# 05_POWER_EFUSE.net
KiCad netlist of a schematic drawn in Altium Designer
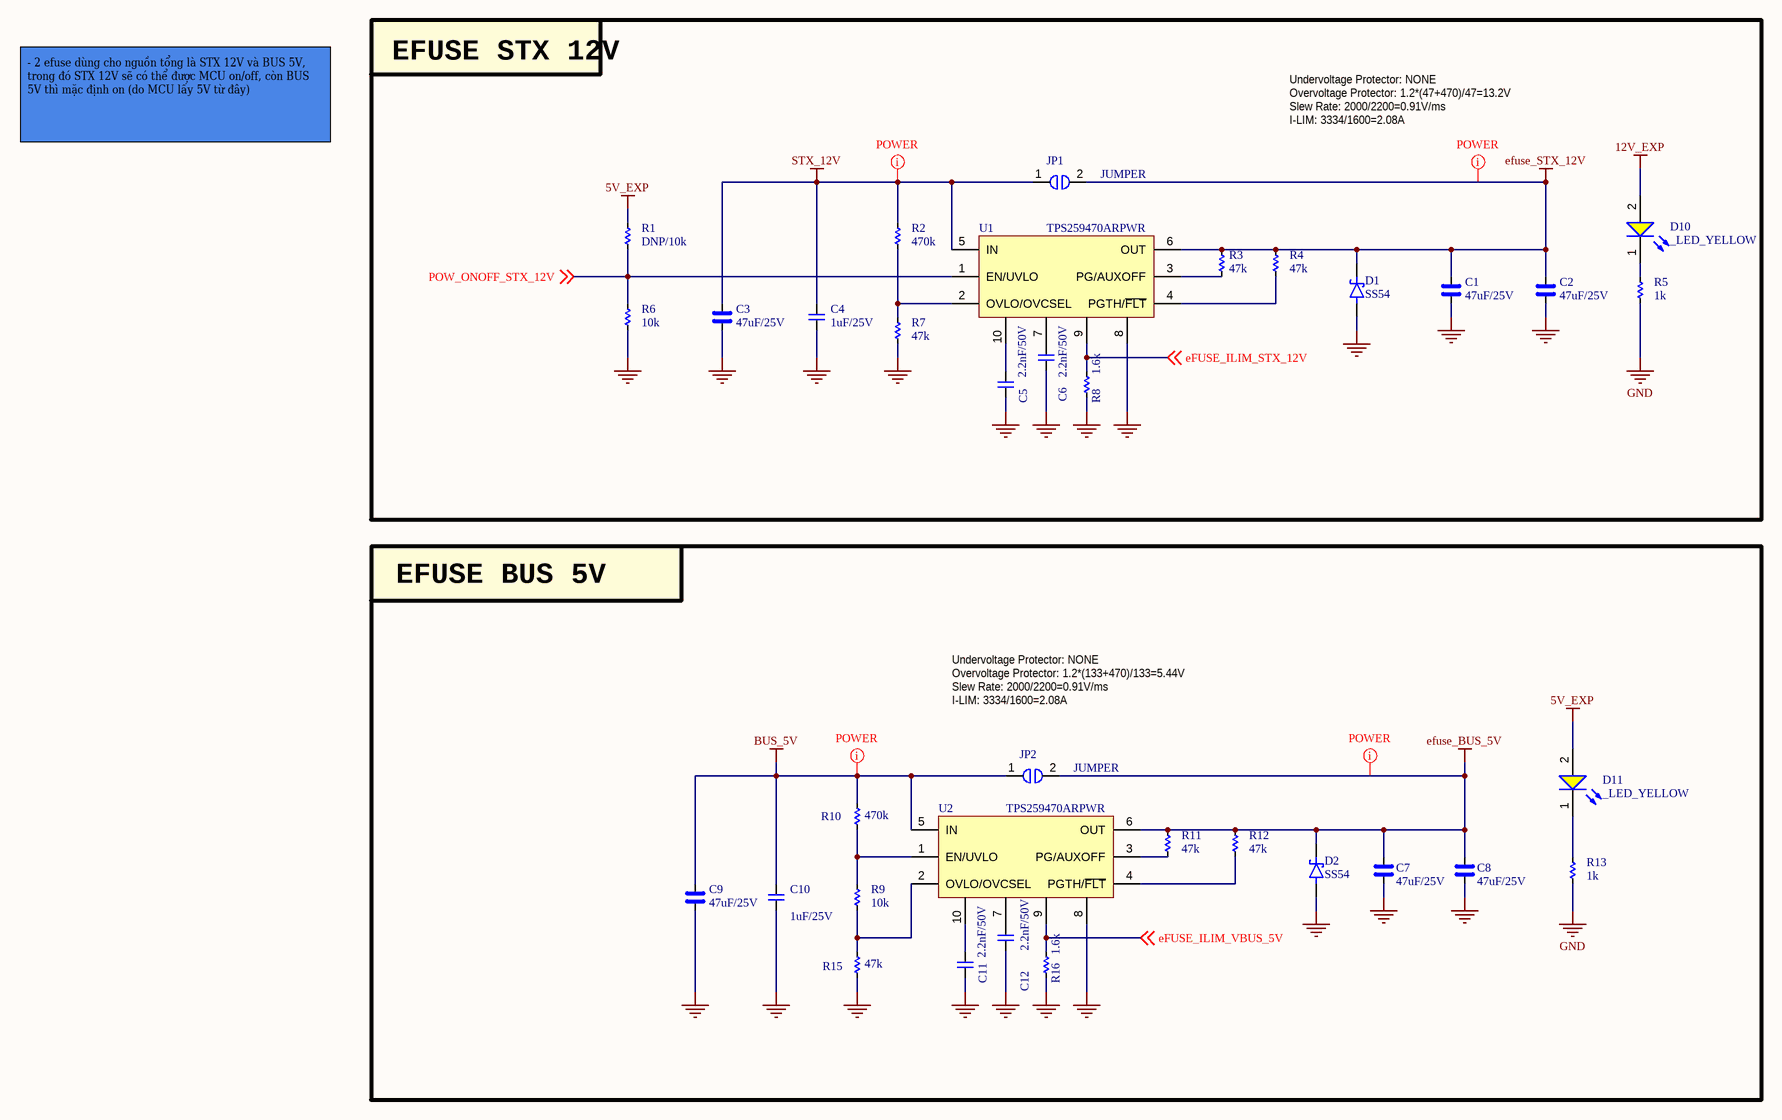
[diagram p0: 05_POWER_EFUSE.SchDoc]

(export (version "E")
  (design (tool "Eeschema 10.0.6"))
  (components
    (comp (ref "C1")
      (value "47uF/25V")
      (footprint "CAP_C_3225X80")
      (description "CAP High Value")
      (libsource (lib "LABLIB") (part "_CAP_C_High_2"))
    )
    (comp (ref "C2")
      (value "47uF/25V")
      (footprint "CAP_C_3225X80")
      (description "CAP High Value")
      (libsource (lib "LABLIB") (part "_CAP_C_High_2"))
    )
    (comp (ref "C3")
      (value "47uF/25V")
      (footprint "CAP_C_3225X80")
      (description "CAP High Value")
      (libsource (lib "LABLIB") (part "_CAP_C_High_2"))
    )
    (comp (ref "C4")
      (value "1uF/25V")
      (footprint "CAP_C_1005X60")
      (description "CAP")
      (libsource (lib "LABLIB") (part "_CAP_C_2"))
    )
    (comp (ref "C5")
      (value "2.2nF/50V")
      (footprint "CAP_C_1005X60")
      (description "CAP")
      (libsource (lib "LABLIB") (part "_CAP_C_2"))
    )
    (comp (ref "C6")
      (value "2.2nF/50V")
      (footprint "CAP_C_1005X60")
      (description "CAP")
      (libsource (lib "LABLIB") (part "_CAP_C_2"))
    )
    (comp (ref "C7")
      (value "47uF/25V")
      (footprint "CAP_C_3225X80")
      (description "CAP High Value")
      (libsource (lib "LABLIB") (part "_CAP_C_High_2"))
    )
    (comp (ref "C8")
      (value "47uF/25V")
      (footprint "CAP_C_3225X80")
      (description "CAP High Value")
      (libsource (lib "LABLIB") (part "_CAP_C_High_2"))
    )
    (comp (ref "C9")
      (value "47uF/25V")
      (footprint "CAP_C_3225X80")
      (description "CAP High Value")
      (libsource (lib "LABLIB") (part "_CAP_C_High_2"))
    )
    (comp (ref "C10")
      (value "1uF/25V")
      (footprint "CAP_C_1005X60")
      (description "CAP")
      (libsource (lib "LABLIB") (part "_CAP_C_2"))
    )
    (comp (ref "C11")
      (value "2.2nF/50V")
      (footprint "CAP_C_1005X60")
      (description "CAP")
      (libsource (lib "LABLIB") (part "_CAP_C_2"))
    )
    (comp (ref "C12")
      (value "2.2nF/50V")
      (footprint "CAP_C_1005X60")
      (description "CAP")
      (libsource (lib "LABLIB") (part "_CAP_C_2"))
    )
    (comp (ref "D1")
      (value "SS54")
      (footprint "DO-214AC_SMA")
      (description "DIODE SCHOTTKY")
      (libsource (lib "LABLIB") (part "DIODE SCHOTTKY"))
    )
    (comp (ref "D2")
      (value "SS54")
      (footprint "DO-214AC_SMA")
      (description "DIODE SCHOTTKY")
      (libsource (lib "LABLIB") (part "DIODE SCHOTTKY"))
    )
    (comp (ref "D10")
      (value "_LED_YELLOW")
      (footprint "LED_0603")
      (libsource (lib "LABLIB") (part "_LED_YELLOW"))
    )
    (comp (ref "D11")
      (value "_LED_YELLOW")
      (footprint "LED_0603")
      (libsource (lib "LABLIB") (part "_LED_YELLOW"))
    )
    (comp (ref "JP1")
      (value "JUMPER")
      (footprint "JUMPER_1608")
      (libsource (lib "BEE-DAL_EXP_sche") (part "JUMPER_1_1"))
    )
    (comp (ref "JP2")
      (value "JUMPER")
      (footprint "JUMPER_1608")
      (libsource (lib "BEE-DAL_EXP_sche") (part "JUMPER_1_1"))
    )
    (comp (ref "R1")
      (value "DNP/10k")
      (footprint "RES_C_1005X40")
      (description "RES")
      (libsource (lib "LABLIB") (part "_RES_B_2"))
    )
    (comp (ref "R2")
      (value "470k")
      (footprint "RES_C_1005X40")
      (description "RES")
      (libsource (lib "LABLIB") (part "_RES_B_2"))
    )
    (comp (ref "R3")
      (value "47k")
      (footprint "RES_C_1005X40")
      (description "RES")
      (libsource (lib "LABLIB") (part "_RES_B_2"))
    )
    (comp (ref "R4")
      (value "47k")
      (footprint "RES_C_1005X40")
      (description "RES")
      (libsource (lib "LABLIB") (part "_RES_B_2"))
    )
    (comp (ref "R5")
      (value "1k")
      (footprint "RES_C_1005X40")
      (description "RES")
      (libsource (lib "LABLIB") (part "_RES_B_2"))
    )
    (comp (ref "R6")
      (value "10k")
      (footprint "RES_C_1005X40")
      (description "RES")
      (libsource (lib "LABLIB") (part "_RES_B_2"))
    )
    (comp (ref "R7")
      (value "47k")
      (footprint "RES_C_1005X40")
      (description "RES")
      (libsource (lib "LABLIB") (part "_RES_B_2"))
    )
    (comp (ref "R8")
      (value "1.6k")
      (footprint "RES_C_1005X40")
      (description "RES")
      (libsource (lib "LABLIB") (part "_RES_B_2"))
    )
    (comp (ref "R9")
      (value "10k")
      (footprint "RES_C_1005X40")
      (description "RES")
      (libsource (lib "LABLIB") (part "_RES_B_2"))
    )
    (comp (ref "R10")
      (value "470k")
      (footprint "RES_C_1005X40")
      (description "RES")
      (libsource (lib "LABLIB") (part "_RES_B_2"))
    )
    (comp (ref "R11")
      (value "47k")
      (footprint "RES_C_1005X40")
      (description "RES")
      (libsource (lib "LABLIB") (part "_RES_B_2"))
    )
    (comp (ref "R12")
      (value "47k")
      (footprint "RES_C_1005X40")
      (description "RES")
      (libsource (lib "LABLIB") (part "_RES_B_2"))
    )
    (comp (ref "R13")
      (value "1k")
      (footprint "RES_C_1005X40")
      (description "RES")
      (libsource (lib "LABLIB") (part "_RES_B_2"))
    )
    (comp (ref "R15")
      (value "47k")
      (footprint "RES_C_1005X40")
      (description "RES")
      (libsource (lib "LABLIB") (part "_RES_B_2"))
    )
    (comp (ref "R16")
      (value "1.6k")
      (footprint "RES_C_1005X40")
      (description "RES")
      (libsource (lib "LABLIB") (part "_RES_B_2"))
    )
    (comp (ref "U1")
      (value "TPS259470ARPWR")
      (footprint "VQFN-HR-10")
      (libsource (lib "BEE-DAL_EXP_sche") (part "TPS259470ARPWR"))
    )
    (comp (ref "U2")
      (value "TPS259470ARPWR")
      (footprint "VQFN-HR-10")
      (libsource (lib "BEE-DAL_EXP_sche") (part "TPS259470ARPWR"))
    )
  )
  (nets
    (net (code "1") (name "5V_EXP") (class "Default")
      (node (ref "D11") (pin "2") (pinfunction "A_2") (pintype "passive"))
      (node (ref "R1") (pin "1") (pinfunction "1_1") (pintype "passive"))
    )
    (net (code "2") (name "12V_EXP") (class "Default")
      (node (ref "D10") (pin "2") (pinfunction "A_2") (pintype "passive"))
    )
    (net (code "3") (name "BUS_5V") (class "Default")
      (node (ref "C10") (pin "2") (pinfunction "2_2") (pintype "passive"))
      (node (ref "C9") (pin "2") (pinfunction "2_2") (pintype "passive"))
      (node (ref "JP2") (pin "1") (pinfunction "1_1") (pintype "passive"))
      (node (ref "R10") (pin "2") (pinfunction "2_2") (pintype "passive"))
      (node (ref "U2") (pin "5") (pinfunction "IN_5") (pintype "passive"))
    )
    (net (code "4") (name "GND") (class "Default")
      (node (ref "C1") (pin "1") (pinfunction "1_1") (pintype "passive"))
      (node (ref "C10") (pin "1") (pinfunction "1_1") (pintype "passive"))
      (node (ref "C11") (pin "1") (pinfunction "1_1") (pintype "passive"))
      (node (ref "C12") (pin "1") (pinfunction "1_1") (pintype "passive"))
      (node (ref "C2") (pin "1") (pinfunction "1_1") (pintype "passive"))
      (node (ref "C3") (pin "1") (pinfunction "1_1") (pintype "passive"))
      (node (ref "C4") (pin "1") (pinfunction "1_1") (pintype "passive"))
      (node (ref "C5") (pin "1") (pinfunction "1_1") (pintype "passive"))
      (node (ref "C6") (pin "1") (pinfunction "1_1") (pintype "passive"))
      (node (ref "C7") (pin "1") (pinfunction "1_1") (pintype "passive"))
      (node (ref "C8") (pin "1") (pinfunction "1_1") (pintype "passive"))
      (node (ref "C9") (pin "1") (pinfunction "1_1") (pintype "passive"))
      (node (ref "D1") (pin "2") (pinfunction "A_2") (pintype "passive"))
      (node (ref "D2") (pin "2") (pinfunction "A_2") (pintype "passive"))
      (node (ref "R13") (pin "1") (pinfunction "1_1") (pintype "passive"))
      (node (ref "R15") (pin "1") (pinfunction "1_1") (pintype "passive"))
      (node (ref "R16") (pin "1") (pinfunction "1_1") (pintype "passive"))
      (node (ref "R5") (pin "1") (pinfunction "1_1") (pintype "passive"))
      (node (ref "R6") (pin "2") (pinfunction "2_2") (pintype "passive"))
      (node (ref "R7") (pin "1") (pinfunction "1_1") (pintype "passive"))
      (node (ref "R8") (pin "1") (pinfunction "1_1") (pintype "passive"))
      (node (ref "U1") (pin "8") (pinfunction "8_8") (pintype "passive"))
      (node (ref "U2") (pin "8") (pinfunction "8_8") (pintype "passive"))
    )
    (net (code "5") (name "Net-(C5-Pad2)") (class "Default")
      (node (ref "C5") (pin "2") (pinfunction "2_2") (pintype "passive"))
      (node (ref "U1") (pin "10") (pinfunction "10_10") (pintype "passive"))
    )
    (net (code "6") (name "Net-(C6-Pad2)") (class "Default")
      (node (ref "C6") (pin "2") (pinfunction "2_2") (pintype "passive"))
      (node (ref "U1") (pin "7") (pinfunction "7_7") (pintype "passive"))
    )
    (net (code "7") (name "Net-(C11-Pad2)") (class "Default")
      (node (ref "C11") (pin "2") (pinfunction "2_2") (pintype "passive"))
      (node (ref "U2") (pin "10") (pinfunction "10_10") (pintype "passive"))
    )
    (net (code "8") (name "Net-(C12-Pad2)") (class "Default")
      (node (ref "C12") (pin "2") (pinfunction "2_2") (pintype "passive"))
      (node (ref "U2") (pin "7") (pinfunction "7_7") (pintype "passive"))
    )
    (net (code "9") (name "Net-(D10-K)") (class "Default")
      (node (ref "D10") (pin "1") (pinfunction "K_1") (pintype "passive"))
      (node (ref "R5") (pin "2") (pinfunction "2_2") (pintype "passive"))
    )
    (net (code "10") (name "Net-(D11-K)") (class "Default")
      (node (ref "D11") (pin "1") (pinfunction "K_1") (pintype "passive"))
      (node (ref "R13") (pin "2") (pinfunction "2_2") (pintype "passive"))
    )
    (net (code "11") (name "Net-(U1-OVLO{slash}OVCSEL)") (class "Default")
      (node (ref "R2") (pin "1") (pinfunction "1_1") (pintype "passive"))
      (node (ref "R7") (pin "2") (pinfunction "2_2") (pintype "passive"))
      (node (ref "U1") (pin "2") (pinfunction "OVLO/OVCSEL_2") (pintype "passive"))
    )
    (net (code "12") (name "Net-(U1-PGTH{slash}~{FLT})") (class "Default")
      (node (ref "R4") (pin "1") (pinfunction "1_1") (pintype "passive"))
      (node (ref "U1") (pin "4") (pinfunction "PGTH/~{FLT}_4") (pintype "passive"))
    )
    (net (code "13") (name "Net-(U1-PG{slash}AUXOFF)") (class "Default")
      (node (ref "R3") (pin "1") (pinfunction "1_1") (pintype "passive"))
      (node (ref "U1") (pin "3") (pinfunction "PG/AUXOFF_3") (pintype "passive"))
    )
    (net (code "14") (name "Net-(U2-EN{slash}UVLO)") (class "Default")
      (node (ref "R10") (pin "1") (pinfunction "1_1") (pintype "passive"))
      (node (ref "R9") (pin "2") (pinfunction "2_2") (pintype "passive"))
      (node (ref "U2") (pin "1") (pinfunction "EN/UVLO_1") (pintype "passive"))
    )
    (net (code "15") (name "Net-(U2-OVLO{slash}OVCSEL)") (class "Default")
      (node (ref "R15") (pin "2") (pinfunction "2_2") (pintype "passive"))
      (node (ref "R9") (pin "1") (pinfunction "1_1") (pintype "passive"))
      (node (ref "U2") (pin "2") (pinfunction "OVLO/OVCSEL_2") (pintype "passive"))
    )
    (net (code "16") (name "Net-(U2-PGTH{slash}~{FLT})") (class "Default")
      (node (ref "R12") (pin "1") (pinfunction "1_1") (pintype "passive"))
      (node (ref "U2") (pin "4") (pinfunction "PGTH/~{FLT}_4") (pintype "passive"))
    )
    (net (code "17") (name "Net-(U2-PG{slash}AUXOFF)") (class "Default")
      (node (ref "R11") (pin "1") (pinfunction "1_1") (pintype "passive"))
      (node (ref "U2") (pin "3") (pinfunction "PG/AUXOFF_3") (pintype "passive"))
    )
    (net (code "18") (name "POW_ONOFF_STX_12V") (class "Default")
      (node (ref "R1") (pin "2") (pinfunction "2_2") (pintype "passive"))
      (node (ref "R6") (pin "1") (pinfunction "1_1") (pintype "passive"))
      (node (ref "U1") (pin "1") (pinfunction "EN/UVLO_1") (pintype "passive"))
    )
    (net (code "19") (name "STX_12V") (class "Default")
      (node (ref "C3") (pin "2") (pinfunction "2_2") (pintype "passive"))
      (node (ref "C4") (pin "2") (pinfunction "2_2") (pintype "passive"))
      (node (ref "JP1") (pin "1") (pinfunction "1_1") (pintype "passive"))
      (node (ref "R2") (pin "2") (pinfunction "2_2") (pintype "passive"))
      (node (ref "U1") (pin "5") (pinfunction "IN_5") (pintype "passive"))
    )
    (net (code "20") (name "eFUSE_ILIM_STX_12V") (class "Default")
      (node (ref "R8") (pin "2") (pinfunction "2_2") (pintype "passive"))
      (node (ref "U1") (pin "9") (pinfunction "9_9") (pintype "passive"))
    )
    (net (code "21") (name "eFUSE_ILIM_VBUS_5V") (class "Default")
      (node (ref "R16") (pin "2") (pinfunction "2_2") (pintype "passive"))
      (node (ref "U2") (pin "9") (pinfunction "9_9") (pintype "passive"))
    )
    (net (code "22") (name "efuse_BUS_5V") (class "Default")
      (node (ref "C7") (pin "2") (pinfunction "2_2") (pintype "passive"))
      (node (ref "C8") (pin "2") (pinfunction "2_2") (pintype "passive"))
      (node (ref "D2") (pin "1") (pinfunction "K_1") (pintype "passive"))
      (node (ref "JP2") (pin "2") (pinfunction "2_2") (pintype "passive"))
      (node (ref "R11") (pin "2") (pinfunction "2_2") (pintype "passive"))
      (node (ref "R12") (pin "2") (pinfunction "2_2") (pintype "passive"))
      (node (ref "U2") (pin "6") (pinfunction "OUT_6") (pintype "passive"))
    )
    (net (code "23") (name "efuse_STX_12V") (class "Default")
      (node (ref "C1") (pin "2") (pinfunction "2_2") (pintype "passive"))
      (node (ref "C2") (pin "2") (pinfunction "2_2") (pintype "passive"))
      (node (ref "D1") (pin "1") (pinfunction "K_1") (pintype "passive"))
      (node (ref "JP1") (pin "2") (pinfunction "2_2") (pintype "passive"))
      (node (ref "R3") (pin "2") (pinfunction "2_2") (pintype "passive"))
      (node (ref "R4") (pin "2") (pinfunction "2_2") (pintype "passive"))
      (node (ref "U1") (pin "6") (pinfunction "OUT_6") (pintype "passive"))
    )
  )
)
